# V5_8-18-09-30.net
KiCad netlist of a schematic drawn in EAGLE
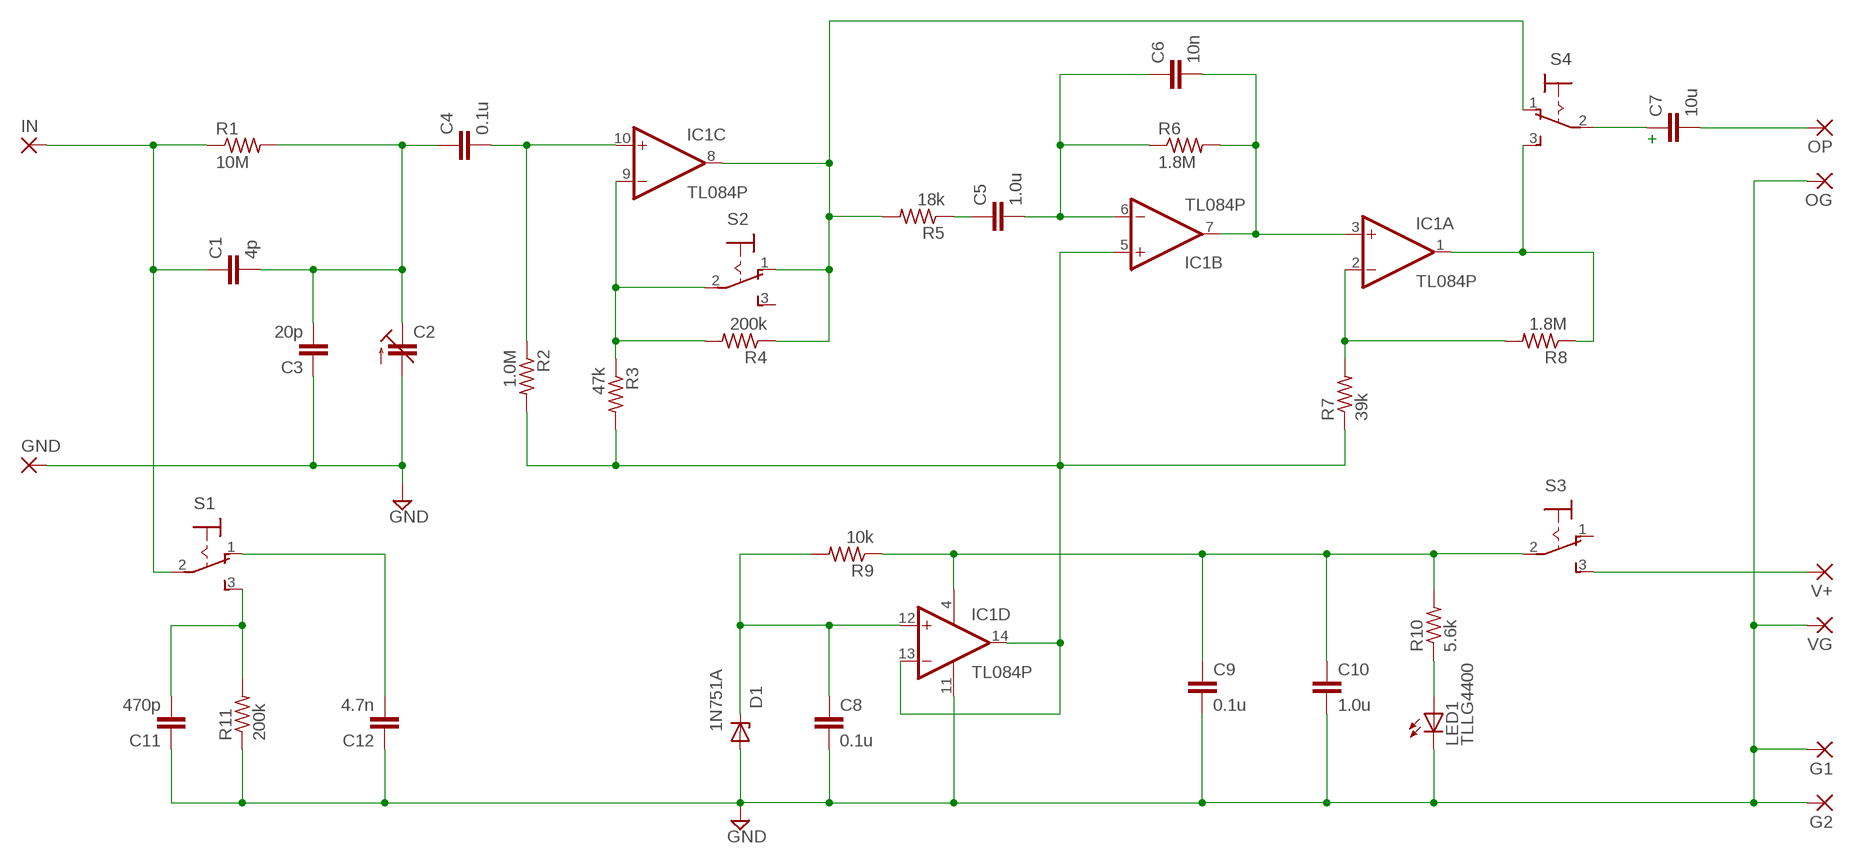
[diagram p0: schematic, sheet 1]

(export (version "E")
  (design (tool "Eeschema 10.0.6"))
  (components
    (comp (ref "C1")
      (value "4p")
      (footprint "eagle-import:C050-024X044")
      (libsource (lib "eagle-import") (part "C-EU050-024X044"))
    )
    (comp (ref "C2")
      (value "C-TRIMMGKG20015")
      (footprint "eagle-import:GKG20015")
      (libsource (lib "eagle-import") (part "C-TRIMMGKG20015"))
    )
    (comp (ref "C3")
      (value "20p")
      (footprint "eagle-import:C050-024X044")
      (libsource (lib "eagle-import") (part "C-EU050-024X044"))
    )
    (comp (ref "C4")
      (value "0.1u")
      (footprint "eagle-import:C050-024X044")
      (libsource (lib "eagle-import") (part "C-EU050-024X044"))
    )
    (comp (ref "C5")
      (value "1.0u")
      (footprint "eagle-import:C050-024X044")
      (libsource (lib "eagle-import") (part "C-EU050-024X044"))
    )
    (comp (ref "C6")
      (value "10n")
      (footprint "eagle-import:C050-024X044")
      (libsource (lib "eagle-import") (part "C-EU050-024X044"))
    )
    (comp (ref "C7")
      (value "10u")
      (footprint "eagle-import:C050-024X044")
      (libsource (lib "eagle-import") (part "C-EU050-024X044"))
    )
    (comp (ref "C8")
      (value "0.1u")
      (footprint "eagle-import:C050-024X044")
      (libsource (lib "eagle-import") (part "C-EU050-024X044"))
    )
    (comp (ref "C9")
      (value "0.1u")
      (footprint "eagle-import:C050-024X044")
      (libsource (lib "eagle-import") (part "C-EU050-024X044"))
    )
    (comp (ref "C10")
      (value "1.0u")
      (footprint "eagle-import:C050-024X044")
      (libsource (lib "eagle-import") (part "C-EU050-024X044"))
    )
    (comp (ref "C11")
      (value "470p")
      (footprint "eagle-import:C050-024X044")
      (libsource (lib "eagle-import") (part "C-EU050-024X044"))
    )
    (comp (ref "C12")
      (value "4.7n")
      (footprint "eagle-import:C050-024X044")
      (libsource (lib "eagle-import") (part "C-EU050-024X044"))
    )
    (comp (ref "D1")
      (value "ZENER-DIODEDO35Z10")
      (footprint "eagle-import:DO35Z10")
      (libsource (lib "eagle-import") (part "ZENER-DIODEDO35Z10"))
    )
    (comp (ref "G1")
      (value "2,54/1,1")
      (footprint "eagle-import:2,54_1,1")
      (libsource (lib "eagle-import") (part "2,54/1,1"))
    )
    (comp (ref "G2")
      (value "2,54/1,1")
      (footprint "eagle-import:2,54_1,1")
      (libsource (lib "eagle-import") (part "2,54/1,1"))
    )
    (comp (ref "GND")
      (value "2,54/1,1")
      (footprint "eagle-import:2,54_1,1")
      (libsource (lib "eagle-import") (part "2,54/1,1"))
    )
    (comp (ref "IC1")
      (value "TL084P")
      (footprint "eagle-import:DIL14")
      (libsource (lib "eagle-import") (part "TL084P"))
    )
    (comp (ref "IN")
      (value "2,54/1,1")
      (footprint "eagle-import:2,54_1,1")
      (libsource (lib "eagle-import") (part "2,54/1,1"))
    )
    (comp (ref "LED1")
      (value "TLLG4400")
      (footprint "eagle-import:LED3MM")
      (fields (field (name "MF") "VISHAY SEMICONDUCTOR"))
      (libsource (lib "eagle-import") (part "TLLG4400"))
    )
    (comp (ref "OG")
      (value "2,54/1,1")
      (footprint "eagle-import:2,54_1,1")
      (libsource (lib "eagle-import") (part "2,54/1,1"))
    )
    (comp (ref "OP")
      (value "2,54/1,1")
      (footprint "eagle-import:2,54_1,1")
      (libsource (lib "eagle-import") (part "2,54/1,1"))
    )
    (comp (ref "R1")
      (value "10M")
      (footprint "eagle-import:0207_10")
      (libsource (lib "eagle-import") (part "R-US_0207/10"))
    )
    (comp (ref "R2")
      (value "1.0M")
      (footprint "eagle-import:0207_10")
      (libsource (lib "eagle-import") (part "R-US_0207/10"))
    )
    (comp (ref "R3")
      (value "47k")
      (footprint "eagle-import:0207_10")
      (libsource (lib "eagle-import") (part "R-US_0207/10"))
    )
    (comp (ref "R4")
      (value "200k")
      (footprint "eagle-import:0207_10")
      (libsource (lib "eagle-import") (part "R-US_0207/10"))
    )
    (comp (ref "R5")
      (value "18k")
      (footprint "eagle-import:0207_10")
      (libsource (lib "eagle-import") (part "R-US_0207/10"))
    )
    (comp (ref "R6")
      (value "1.8M")
      (footprint "eagle-import:0207_10")
      (libsource (lib "eagle-import") (part "R-US_0207/10"))
    )
    (comp (ref "R7")
      (value "39k")
      (footprint "eagle-import:0207_10")
      (libsource (lib "eagle-import") (part "R-US_0207/10"))
    )
    (comp (ref "R8")
      (value "1.8M")
      (footprint "eagle-import:0207_10")
      (libsource (lib "eagle-import") (part "R-US_0207/10"))
    )
    (comp (ref "R9")
      (value "10k")
      (footprint "eagle-import:0207_10")
      (libsource (lib "eagle-import") (part "R-US_0207/10"))
    )
    (comp (ref "R10")
      (value "5.6k")
      (footprint "eagle-import:0207_10")
      (libsource (lib "eagle-import") (part "R-US_0207/10"))
    )
    (comp (ref "R11")
      (value "200k")
      (footprint "eagle-import:0207_10")
      (libsource (lib "eagle-import") (part "R-US_0207/10"))
    )
    (comp (ref "S1")
      (value "320-916")
      (footprint "eagle-import:320-916")
      (libsource (lib "eagle-import") (part "320-916"))
    )
    (comp (ref "S2")
      (value "320-916")
      (footprint "eagle-import:320-916")
      (libsource (lib "eagle-import") (part "320-916"))
    )
    (comp (ref "S3")
      (value "320-916")
      (footprint "eagle-import:320-916")
      (libsource (lib "eagle-import") (part "320-916"))
    )
    (comp (ref "S4")
      (value "320-916")
      (footprint "eagle-import:320-916")
      (libsource (lib "eagle-import") (part "320-916"))
    )
    (comp (ref "V+")
      (value "2,54/1,1")
      (footprint "eagle-import:2,54_1,1")
      (libsource (lib "eagle-import") (part "2,54/1,1"))
    )
    (comp (ref "VG")
      (value "2,54/1,1")
      (footprint "eagle-import:2,54_1,1")
      (libsource (lib "eagle-import") (part "2,54/1,1"))
    )
  )
  (nets
    (net (code "1") (name "GND") (class "Default")
      (node (ref "C10") (pin "2") (pinfunction "2_2") (pintype "passive"))
      (node (ref "C11") (pin "1") (pinfunction "1_1") (pintype "passive"))
      (node (ref "C12") (pin "1") (pinfunction "1_1") (pintype "passive"))
      (node (ref "C2") (pin "1") (pinfunction "A_1") (pintype "passive"))
      (node (ref "C3") (pin "1") (pinfunction "1_1") (pintype "passive"))
      (node (ref "C8") (pin "2") (pinfunction "2_2") (pintype "passive"))
      (node (ref "C9") (pin "2") (pinfunction "2_2") (pintype "passive"))
      (node (ref "D1") (pin "A") (pinfunction "A_A") (pintype "passive"))
      (node (ref "G1") (pin "1") (pinfunction "P_1") (pintype "passive"))
      (node (ref "G2") (pin "1") (pinfunction "P_1") (pintype "passive"))
      (node (ref "GND") (pin "1") (pinfunction "P_1") (pintype "passive"))
      (node (ref "IC1") (pin "11") (pinfunction "V-_11") (pintype "power_in"))
      (node (ref "LED1") (pin "K") (pinfunction "C_K") (pintype "passive"))
      (node (ref "OG") (pin "1") (pinfunction "P_1") (pintype "passive"))
      (node (ref "R11") (pin "1") (pinfunction "1_1") (pintype "passive"))
      (node (ref "VG") (pin "1") (pinfunction "P_1") (pintype "passive"))
    )
    (net (code "2") (name "Net-(C2-E)") (class "Default")
      (node (ref "C1") (pin "2") (pinfunction "2_2") (pintype "passive"))
      (node (ref "C2") (pin "2") (pinfunction "E_2") (pintype "passive"))
      (node (ref "C3") (pin "2") (pinfunction "2_2") (pintype "passive"))
      (node (ref "C4") (pin "1") (pinfunction "1_1") (pintype "passive"))
      (node (ref "R1") (pin "2") (pinfunction "2_2") (pintype "passive"))
    )
    (net (code "3") (name "Net-(C5-Pad1)") (class "Default")
      (node (ref "C5") (pin "1") (pinfunction "1_1") (pintype "passive"))
      (node (ref "R5") (pin "1") (pinfunction "1_1") (pintype "passive"))
    )
    (net (code "4") (name "Net-(IC1A-+IN)") (class "Default")
      (node (ref "C6") (pin "2") (pinfunction "2_2") (pintype "passive"))
      (node (ref "IC1") (pin "3") (pinfunction "+IN_3") (pintype "input"))
      (node (ref "IC1") (pin "7") (pinfunction "OUT_7") (pintype "output"))
      (node (ref "R6") (pin "2") (pinfunction "2_2") (pintype "passive"))
    )
    (net (code "5") (name "Net-(IC1A--IN)") (class "Default")
      (node (ref "IC1") (pin "2") (pinfunction "-IN_2") (pintype "input"))
      (node (ref "R7") (pin "2") (pinfunction "2_2") (pintype "passive"))
      (node (ref "R8") (pin "2") (pinfunction "2_2") (pintype "passive"))
    )
    (net (code "6") (name "Net-(IC1A-OUT)") (class "Default")
      (node (ref "IC1") (pin "1") (pinfunction "OUT_1") (pintype "output"))
      (node (ref "R8") (pin "1") (pinfunction "1_1") (pintype "passive"))
      (node (ref "S4") (pin "3") (pinfunction "S_3") (pintype "passive"))
    )
    (net (code "7") (name "Net-(IC1B-+IN)") (class "Default")
      (node (ref "IC1") (pin "13") (pinfunction "-IN_13") (pintype "input"))
      (node (ref "IC1") (pin "14") (pinfunction "OUT_14") (pintype "output"))
      (node (ref "IC1") (pin "5") (pinfunction "+IN_5") (pintype "input"))
      (node (ref "R2") (pin "2") (pinfunction "2_2") (pintype "passive"))
      (node (ref "R3") (pin "2") (pinfunction "2_2") (pintype "passive"))
      (node (ref "R7") (pin "1") (pinfunction "1_1") (pintype "passive"))
    )
    (net (code "8") (name "Net-(IC1B--IN)") (class "Default")
      (node (ref "C5") (pin "2") (pinfunction "2_2") (pintype "passive"))
      (node (ref "C6") (pin "1") (pinfunction "1_1") (pintype "passive"))
      (node (ref "IC1") (pin "6") (pinfunction "-IN_6") (pintype "input"))
      (node (ref "R6") (pin "1") (pinfunction "1_1") (pintype "passive"))
    )
    (net (code "9") (name "Net-(IC1C-+IN)") (class "Default")
      (node (ref "C4") (pin "2") (pinfunction "2_2") (pintype "passive"))
      (node (ref "IC1") (pin "10") (pinfunction "+IN_10") (pintype "input"))
      (node (ref "R2") (pin "1") (pinfunction "1_1") (pintype "passive"))
    )
    (net (code "10") (name "Net-(IC1C--IN)") (class "Default")
      (node (ref "IC1") (pin "9") (pinfunction "-IN_9") (pintype "input"))
      (node (ref "R3") (pin "1") (pinfunction "1_1") (pintype "passive"))
      (node (ref "R4") (pin "2") (pinfunction "2_2") (pintype "passive"))
      (node (ref "S2") (pin "2") (pinfunction "P_2") (pintype "passive"))
    )
    (net (code "11") (name "Net-(IC1C-OUT)") (class "Default")
      (node (ref "IC1") (pin "8") (pinfunction "OUT_8") (pintype "output"))
      (node (ref "R4") (pin "1") (pinfunction "1_1") (pintype "passive"))
      (node (ref "R5") (pin "2") (pinfunction "2_2") (pintype "passive"))
      (node (ref "S2") (pin "1") (pinfunction "O_1") (pintype "passive"))
      (node (ref "S4") (pin "1") (pinfunction "O_1") (pintype "passive"))
    )
    (net (code "12") (name "Net-(IC1D-+IN)") (class "Default")
      (node (ref "C8") (pin "1") (pinfunction "1_1") (pintype "passive"))
      (node (ref "D1") (pin "C") (pinfunction "C_C") (pintype "passive"))
      (node (ref "IC1") (pin "12") (pinfunction "+IN_12") (pintype "input"))
      (node (ref "R9") (pin "2") (pinfunction "2_2") (pintype "passive"))
    )
    (net (code "13") (name "Net-(IC1E-V+)") (class "Default")
      (node (ref "C10") (pin "1") (pinfunction "1_1") (pintype "passive"))
      (node (ref "C9") (pin "1") (pinfunction "1_1") (pintype "passive"))
      (node (ref "IC1") (pin "4") (pinfunction "V+_4") (pintype "power_in"))
      (node (ref "R10") (pin "2") (pinfunction "2_2") (pintype "passive"))
      (node (ref "R9") (pin "1") (pinfunction "1_1") (pintype "passive"))
      (node (ref "S3") (pin "2") (pinfunction "P_2") (pintype "passive"))
    )
    (net (code "14") (name "Net-(IN-P)") (class "Default")
      (node (ref "C1") (pin "1") (pinfunction "1_1") (pintype "passive"))
      (node (ref "IN") (pin "1") (pinfunction "P_1") (pintype "passive"))
      (node (ref "R1") (pin "1") (pinfunction "1_1") (pintype "passive"))
      (node (ref "S1") (pin "2") (pinfunction "P_2") (pintype "passive"))
    )
    (net (code "15") (name "Net-(LED1-PadA)") (class "Default")
      (node (ref "LED1") (pin "A") (pinfunction "A_A") (pintype "passive"))
      (node (ref "R10") (pin "1") (pinfunction "1_1") (pintype "passive"))
    )
    (net (code "16") (name "Net-(OP-P)") (class "Default")
      (node (ref "C7") (pin "2") (pinfunction "2_2") (pintype "passive"))
      (node (ref "OP") (pin "1") (pinfunction "P_1") (pintype "passive"))
    )
    (net (code "17") (name "Net-(S1-O)") (class "Default")
      (node (ref "C12") (pin "2") (pinfunction "2_2") (pintype "passive"))
      (node (ref "S1") (pin "1") (pinfunction "O_1") (pintype "passive"))
    )
    (net (code "18") (name "Net-(S1-S)") (class "Default")
      (node (ref "C11") (pin "2") (pinfunction "2_2") (pintype "passive"))
      (node (ref "R11") (pin "2") (pinfunction "2_2") (pintype "passive"))
      (node (ref "S1") (pin "3") (pinfunction "S_3") (pintype "passive"))
    )
    (net (code "19") (name "Net-(S3-S)") (class "Default")
      (node (ref "S3") (pin "3") (pinfunction "S_3") (pintype "passive"))
      (node (ref "V+") (pin "1") (pinfunction "P_1") (pintype "passive"))
    )
    (net (code "20") (name "Net-(S4-P)") (class "Default")
      (node (ref "C7") (pin "1") (pinfunction "1_1") (pintype "passive"))
      (node (ref "S4") (pin "2") (pinfunction "P_2") (pintype "passive"))
    )
    (net (code "21") (name "unconnected-(S2-S-Pad3)") (class "Default")
      (node (ref "S2") (pin "3") (pinfunction "S_3") (pintype "passive"))
    )
    (net (code "22") (name "unconnected-(S3-O-Pad1)") (class "Default")
      (node (ref "S3") (pin "1") (pinfunction "O_1") (pintype "passive"))
    )
  )
)
